# WDUExtensionBoard_v2.net
KiCad netlist of a schematic drawn in Altium Designer
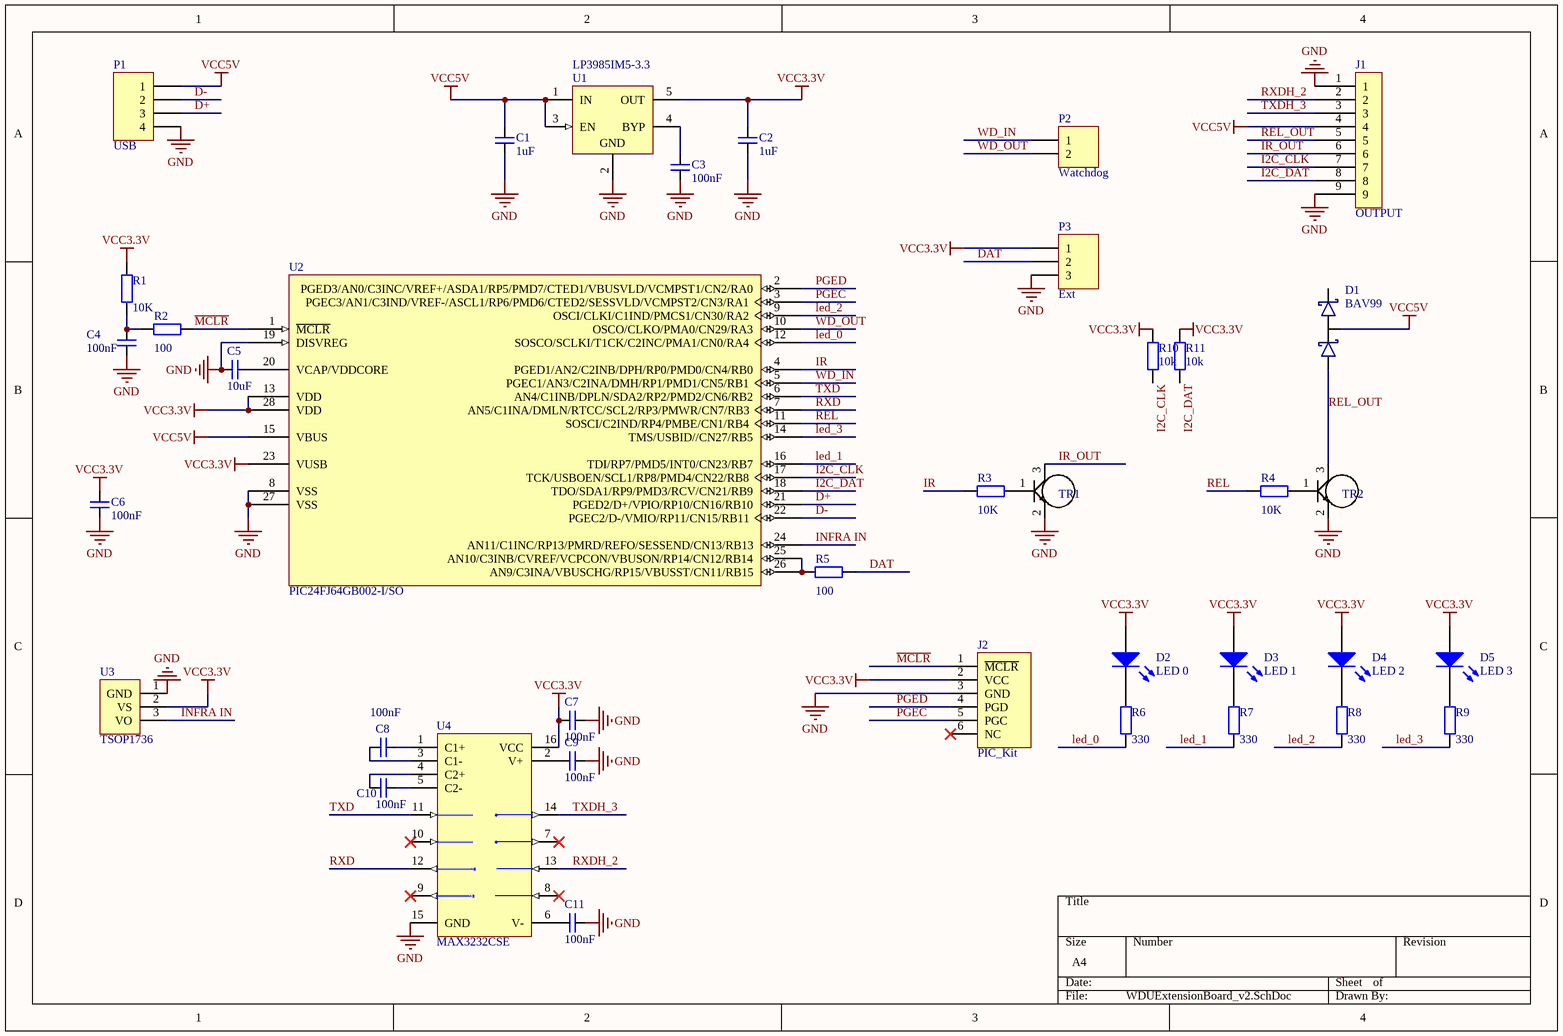
[diagram p0: WDUExtensionBoard_v2.SchDoc]

(export (version "E")
  (design (tool "Eeschema 10.0.6"))
  (components
    (comp (ref "C1")
      (value "1uF")
      (footprint "0805 CAP")
      (description "Capacitor")
      (libsource (lib "EtherIOv2") (part "CAP"))
    )
    (comp (ref "C2")
      (value "1uF")
      (footprint "0805 CAP")
      (description "Capacitor")
      (libsource (lib "EtherIOv2") (part "CAP"))
    )
    (comp (ref "C3")
      (value "100nF")
      (footprint "0805 CAP")
      (description "Capacitor")
      (libsource (lib "EtherIOv2") (part "CAP"))
    )
    (comp (ref "C4")
      (value "100nF")
      (footprint "0805 CAP")
      (description "Capacitor")
      (libsource (lib "EtherIOv2") (part "CAP"))
    )
    (comp (ref "C5")
      (value "10uF")
      (footprint "0805 CAP")
      (description "Capacitor")
      (libsource (lib "EtherIOv2") (part "CAP"))
    )
    (comp (ref "C6")
      (value "100nF")
      (footprint "0805 CAP")
      (description "Capacitor")
      (libsource (lib "EtherIOv2") (part "CAP"))
    )
    (comp (ref "C7")
      (value "100nF")
      (footprint "0805 CAP")
      (description "Capacitor")
      (libsource (lib "EtherIOv2") (part "CAP"))
    )
    (comp (ref "C8")
      (value "100nF")
      (footprint "0805 CAP")
      (description "Capacitor")
      (libsource (lib "EtherIOv2") (part "CAP"))
    )
    (comp (ref "C9")
      (value "100nF")
      (footprint "0805 CAP")
      (description "Capacitor")
      (libsource (lib "EtherIOv2") (part "CAP"))
    )
    (comp (ref "C10")
      (value "100nF")
      (footprint "0805 CAP")
      (description "Capacitor")
      (libsource (lib "EtherIOv2") (part "CAP"))
    )
    (comp (ref "C11")
      (value "100nF")
      (footprint "0805 CAP")
      (description "Capacitor")
      (libsource (lib "EtherIOv2") (part "CAP"))
    )
    (comp (ref "D1")
      (value "BAV99")
      (footprint "SOT23")
      (description "Dual Schottky series - 0.2A, 75V")
      (libsource (lib "EtherIOv2") (part "BAV99"))
    )
    (comp (ref "D2")
      (value "LED 0")
      (footprint "1206 LED Reversed")
      (description "Typical RED, GREEN, YELLOW, AMBER GaAs LED")
      (fields (field (name "PUBLISHER") "Altium Limited"))
      (libsource (lib "Miscellaneous Devices") (part "LED2"))
    )
    (comp (ref "D3")
      (value "LED 1")
      (footprint "1206 LED Reversed")
      (description "Typical RED, GREEN, YELLOW, AMBER GaAs LED")
      (fields (field (name "PUBLISHER") "Altium Limited"))
      (libsource (lib "Miscellaneous Devices") (part "LED2"))
    )
    (comp (ref "D4")
      (value "LED 2")
      (footprint "1206 LED Reversed")
      (description "Typical RED, GREEN, YELLOW, AMBER GaAs LED")
      (fields (field (name "PUBLISHER") "Altium Limited"))
      (libsource (lib "Miscellaneous Devices") (part "LED2"))
    )
    (comp (ref "D5")
      (value "LED 3")
      (footprint "1206 LED Reversed")
      (description "Typical RED, GREEN, YELLOW, AMBER GaAs LED")
      (fields (field (name "PUBLISHER") "Altium Limited"))
      (libsource (lib "Miscellaneous Devices") (part "LED2"))
    )
    (comp (ref "J1")
      (value "OUTPUT")
      (footprint "Euroblock 3.5pitch 9P")
      (libsource (lib "EtherIOv2") (part "Euroblock 9P connector"))
    )
    (comp (ref "J2")
      (value "PIC_Kit")
      (footprint "HDR1X6")
      (description "PIC Kit connector")
      (libsource (lib "EtherIOv2") (part "PIC_Kit"))
    )
    (comp (ref "P1")
      (value "USB")
      (footprint "HDR1X4")
      (description "Header, 4-Pin")
      (fields (field (name "PUBLISHER") "Altium Limited"))
      (libsource (lib "Miscellaneous Connectors") (part "Header 4"))
    )
    (comp (ref "P2")
      (value "Watchdog")
      (footprint "HDR1X2")
      (description "Header, 2-Pin")
      (fields (field (name "PUBLISHER") "Altium Limited"))
      (libsource (lib "Miscellaneous Connectors") (part "Header 2"))
    )
    (comp (ref "P3")
      (value "Ext")
      (footprint "HDR1X3")
      (description "Header, 3-Pin")
      (fields (field (name "PUBLISHER") "Altium Limited"))
      (libsource (lib "Miscellaneous Connectors") (part "Header 3"))
    )
    (comp (ref "R1")
      (value "10K")
      (footprint "0805 RES")
      (description "Resistor")
      (fields (field (name "PUBLISHER") "Altium Limited"))
      (libsource (lib "") (part "RES_1"))
    )
    (comp (ref "R2")
      (value "100")
      (footprint "0805 RES")
      (description "Resistor")
      (fields (field (name "PUBLISHER") "Altium Limited"))
      (libsource (lib "") (part "RES_2"))
    )
    (comp (ref "R3")
      (value "10K")
      (footprint "0805 RES")
      (description "Resistor")
      (fields (field (name "PUBLISHER") "Altium Limited"))
      (libsource (lib "") (part "RES_2"))
    )
    (comp (ref "R4")
      (value "10K")
      (footprint "0805 RES")
      (description "Resistor")
      (fields (field (name "PUBLISHER") "Altium Limited"))
      (libsource (lib "") (part "RES_2"))
    )
    (comp (ref "R5")
      (value "100")
      (footprint "0805 RES")
      (description "Resistor")
      (fields (field (name "PUBLISHER") "Altium Limited"))
      (libsource (lib "") (part "RES_2"))
    )
    (comp (ref "R6")
      (value "330")
      (footprint "0805 RES")
      (description "Resistor")
      (fields (field (name "PUBLISHER") "Altium Limited"))
      (libsource (lib "EtherIOv2") (part "RES"))
    )
    (comp (ref "R7")
      (value "330")
      (footprint "0805 RES")
      (description "Resistor")
      (fields (field (name "PUBLISHER") "Altium Limited"))
      (libsource (lib "EtherIOv2") (part "RES"))
    )
    (comp (ref "R8")
      (value "330")
      (footprint "0805 RES")
      (description "Resistor")
      (fields (field (name "PUBLISHER") "Altium Limited"))
      (libsource (lib "EtherIOv2") (part "RES"))
    )
    (comp (ref "R9")
      (value "330")
      (footprint "0805 RES")
      (description "Resistor")
      (fields (field (name "PUBLISHER") "Altium Limited"))
      (libsource (lib "EtherIOv2") (part "RES"))
    )
    (comp (ref "R10")
      (value "10k")
      (footprint "FP_0603_RES")
      (description "Resistor")
      (libsource (lib "Miscellaneous Devices") (part "Res3"))
    )
    (comp (ref "R11")
      (value "10k")
      (footprint "FP_0603_RES")
      (description "Resistor")
      (libsource (lib "Miscellaneous Devices") (part "Res3"))
    )
    (comp (ref "TR1")
      (value "BC846")
      (footprint "SOT23")
      (description "NPN Transistor, 80 V, SOT23")
      (libsource (lib "Waterstars") (part "BC846"))
    )
    (comp (ref "TR2")
      (value "BC846")
      (footprint "SOT23")
      (description "NPN Transistor, 80 V, SOT23")
      (libsource (lib "Waterstars") (part "BC846"))
    )
    (comp (ref "U1")
      (value "LP3985IM5-3.3")
      (footprint "MF05A_N")
      (description "Micropower, 150mA Low-Noise Ultra Low-Dropout CMOS Voltage Regulator")
      (fields
        (field (name "MANUFACTURER") "National Semiconductor")
        (field (name "DIGIKEYPARTNUMBER") "LP3985IM5-3.3CT-ND")
        (field (name "PUBLISHER") "Altium Limited")
      )
      (libsource (lib "NSC LDO") (part "LP3985IM5-3.3"))
    )
    (comp (ref "U2")
      (value "PIC24FJ64GB002-I/SO")
      (footprint "SSOP-28")
      (fields (field (name "PUBLISHER") "Altium Limited"))
      (libsource (lib "Waterstars") (part "PIC24FJ64GB002-I/SO"))
    )
    (comp (ref "U3")
      (value "TSOP1736")
      (footprint "TSOP17xx")
      (description "IR Receiver, 3-Pin")
      (fields (field (name "PUBLISHER") "Altium Limited"))
      (libsource (lib "EtherIOv2") (part "TSOP17xx"))
    )
    (comp (ref "U4")
      (value "MAX3232CSE")
      (footprint "NSO16_M")
      (description "3.0V TO 5.5V, Low-Power, up to 1Mbps, True RS-232 Transceiver Using Four 0.1µF External Capacitor")
      (fields (field (name "PUBLISHER") "Altium Limited"))
      (libsource (lib "Maxim Communication Transceiver") (part "MAX3232CSE"))
    )
  )
  (nets
    (net (code "1") (name "/D+") (class "Default")
      (node (ref "P1") (pin "3") (pinfunction "3_3") (pintype "passive"))
      (node (ref "U2") (pin "21") (pinfunction "PGED2/D+/VPIO/RP10/CN16/RB10_21") (pintype "bidirectional"))
    )
    (net (code "2") (name "/D-") (class "Default")
      (node (ref "P1") (pin "2") (pinfunction "2_2") (pintype "passive"))
      (node (ref "U2") (pin "22") (pinfunction "PGEC2/D-/VMIO/RP11/CN15/RB11_22") (pintype "bidirectional"))
    )
    (net (code "3") (name "/DAT") (class "Default")
      (node (ref "P3") (pin "2") (pinfunction "2_2") (pintype "passive"))
      (node (ref "R5") (pin "1") (pinfunction "1_1") (pintype "passive"))
    )
    (net (code "4") (name "/I2C_CLK") (class "Default")
      (node (ref "J1") (pin "7") (pinfunction "7_7") (pintype "passive"))
      (node (ref "R10") (pin "2") (pinfunction "2_2") (pintype "passive"))
      (node (ref "U2") (pin "17") (pinfunction "TCK/USBOEN/SCL1/RP8/PMD4/CN22/RB8_17") (pintype "bidirectional"))
    )
    (net (code "5") (name "/I2C_DAT") (class "Default")
      (node (ref "J1") (pin "8") (pinfunction "8_8") (pintype "passive"))
      (node (ref "R11") (pin "2") (pinfunction "2_2") (pintype "passive"))
      (node (ref "U2") (pin "18") (pinfunction "TDO/SDA1/RP9/PMD3/RCV/CN21/RB9_18") (pintype "bidirectional"))
    )
    (net (code "6") (name "/INFRA IN") (class "Default")
      (node (ref "U2") (pin "24") (pinfunction "AN11/C1INC/RP13/PMRD/REFO/SESSEND/CN13/RB13_24") (pintype "bidirectional"))
      (node (ref "U3") (pin "3") (pinfunction "VO_3") (pintype "passive"))
    )
    (net (code "7") (name "/IR") (class "Default")
      (node (ref "R3") (pin "2") (pinfunction "2_2") (pintype "passive"))
      (node (ref "U2") (pin "4") (pinfunction "PGED1/AN2/C2INB/DPH/RP0/PMD0/CN4/RB0_4") (pintype "bidirectional"))
    )
    (net (code "8") (name "/IR_OUT") (class "Default")
      (node (ref "J1") (pin "6") (pinfunction "6_6") (pintype "passive"))
      (node (ref "TR1") (pin "3") (pinfunction "2_3") (pintype "passive"))
    )
    (net (code "9") (name "/PGEC") (class "Default")
      (node (ref "J2") (pin "5") (pinfunction "PGC_5") (pintype "passive"))
      (node (ref "U2") (pin "3") (pinfunction "PGEC3/AN1/C3IND/VREF-/ASCL1/RP6/PMD6/CTED2/SESSVLD/VCMPST2/CN3/RA1_3") (pintype "bidirectional"))
    )
    (net (code "10") (name "/PGED") (class "Default")
      (node (ref "J2") (pin "4") (pinfunction "PGD_4") (pintype "passive"))
      (node (ref "U2") (pin "2") (pinfunction "PGED3/AN0/C3INC/VREF+/ASDA1/RP5/PMD7/CTED1/VBUSVLD/VCMPST1/CN2/RA0_2") (pintype "bidirectional"))
    )
    (net (code "11") (name "/REL") (class "Default")
      (node (ref "R4") (pin "2") (pinfunction "2_2") (pintype "passive"))
      (node (ref "U2") (pin "11") (pinfunction "SOSCI/C2IND/RP4/PMBE/CN1/RB4_11") (pintype "bidirectional"))
    )
    (net (code "12") (name "/REL_OUT") (class "Default")
      (node (ref "D1") (pin "1") (pintype "passive"))
      (node (ref "J1") (pin "5") (pinfunction "5_5") (pintype "passive"))
      (node (ref "TR2") (pin "3") (pinfunction "2_3") (pintype "passive"))
    )
    (net (code "13") (name "/RXD") (class "Default")
      (node (ref "U2") (pin "7") (pinfunction "AN5/C1INA/DMLN/RTCC/SCL2/RP3/PMWR/CN7/RB3_7") (pintype "bidirectional"))
      (node (ref "U4") (pin "12") (pinfunction "R1OUT_12") (pintype "output"))
    )
    (net (code "14") (name "/RXDH_2") (class "Default")
      (node (ref "J1") (pin "2") (pinfunction "2_2") (pintype "passive"))
      (node (ref "U4") (pin "13") (pinfunction "R1IN_13") (pintype "input"))
    )
    (net (code "15") (name "/TXD") (class "Default")
      (node (ref "U2") (pin "6") (pinfunction "AN4/C1INB/DPLN/SDA2/RP2/PMD2/CN6/RB2_6") (pintype "bidirectional"))
      (node (ref "U4") (pin "11") (pinfunction "T1IN_11") (pintype "input"))
    )
    (net (code "16") (name "/TXDH_3") (class "Default")
      (node (ref "J1") (pin "3") (pinfunction "3_3") (pintype "passive"))
      (node (ref "U4") (pin "14") (pinfunction "T1OUT_14") (pintype "output"))
    )
    (net (code "17") (name "/WD_IN") (class "Default")
      (node (ref "P2") (pin "1") (pinfunction "1_1") (pintype "passive"))
      (node (ref "U2") (pin "5") (pinfunction "PGEC1/AN3/C2INA/DMH/RP1/PMD1/CN5/RB1_5") (pintype "bidirectional"))
    )
    (net (code "18") (name "/WD_OUT") (class "Default")
      (node (ref "P2") (pin "2") (pinfunction "2_2") (pintype "passive"))
      (node (ref "U2") (pin "10") (pinfunction "OSCO/CLKO/PMA0/CN29/RA3_10") (pintype "bidirectional"))
    )
    (net (code "19") (name "/led_0") (class "Default")
      (node (ref "R6") (pin "2") (pinfunction "2_2") (pintype "passive"))
      (node (ref "U2") (pin "12") (pinfunction "SOSCO/SCLKI/T1CK/C2INC/PMA1/CN0/RA4_12") (pintype "bidirectional"))
    )
    (net (code "20") (name "/led_1") (class "Default")
      (node (ref "R7") (pin "2") (pinfunction "2_2") (pintype "passive"))
      (node (ref "U2") (pin "16") (pinfunction "TDI/RP7/PMD5/INT0/CN23/RB7_16") (pintype "bidirectional"))
    )
    (net (code "21") (name "/led_2") (class "Default")
      (node (ref "R8") (pin "2") (pinfunction "2_2") (pintype "passive"))
      (node (ref "U2") (pin "9") (pinfunction "OSCI/CLKI/C1IND/PMCS1/CN30/RA2_9") (pintype "bidirectional"))
    )
    (net (code "22") (name "/led_3") (class "Default")
      (node (ref "R9") (pin "2") (pinfunction "2_2") (pintype "passive"))
      (node (ref "U2") (pin "14") (pinfunction "TMS/USBID//CN27/RB5_14") (pintype "bidirectional"))
    )
    (net (code "23") (name "/~{MCLR}") (class "Default")
      (node (ref "J2") (pin "1") (pinfunction "~{MCLR}_1") (pintype "passive"))
      (node (ref "R2") (pin "1") (pinfunction "1_1") (pintype "passive"))
      (node (ref "U2") (pin "1") (pinfunction "~{MCLR}_1") (pintype "input"))
    )
    (net (code "24") (name "GND") (class "Default")
      (node (ref "C1") (pin "1") (pinfunction "A_1") (pintype "passive"))
      (node (ref "C11") (pin "2") (pinfunction "B_2") (pintype "passive"))
      (node (ref "C2") (pin "1") (pinfunction "A_1") (pintype "passive"))
      (node (ref "C3") (pin "1") (pinfunction "A_1") (pintype "passive"))
      (node (ref "C4") (pin "1") (pinfunction "A_1") (pintype "passive"))
      (node (ref "C5") (pin "2") (pinfunction "B_2") (pintype "passive"))
      (node (ref "C6") (pin "1") (pinfunction "A_1") (pintype "passive"))
      (node (ref "C7") (pin "2") (pinfunction "B_2") (pintype "passive"))
      (node (ref "C9") (pin "2") (pinfunction "B_2") (pintype "passive"))
      (node (ref "J1") (pin "1") (pinfunction "1_1") (pintype "passive"))
      (node (ref "J1") (pin "9") (pinfunction "9_9") (pintype "passive"))
      (node (ref "J2") (pin "3") (pinfunction "GND_3") (pintype "passive"))
      (node (ref "P1") (pin "4") (pinfunction "4_4") (pintype "passive"))
      (node (ref "P3") (pin "3") (pinfunction "3_3") (pintype "passive"))
      (node (ref "TR1") (pin "2") (pinfunction "1_2") (pintype "passive"))
      (node (ref "TR2") (pin "2") (pinfunction "1_2") (pintype "passive"))
      (node (ref "U1") (pin "2") (pinfunction "GND_2") (pintype "power_in"))
      (node (ref "U2") (pin "19") (pinfunction "DISVREG_19") (pintype "input"))
      (node (ref "U2") (pin "27") (pinfunction "VSS_27") (pintype "power_in"))
      (node (ref "U2") (pin "8") (pinfunction "VSS_8") (pintype "power_in"))
      (node (ref "U3") (pin "1") (pinfunction "GND_1") (pintype "passive"))
      (node (ref "U4") (pin "15") (pinfunction "GND_15") (pintype "power_in"))
    )
    (net (code "25") (name "Net-(C3-B)") (class "Default")
      (node (ref "C3") (pin "2") (pinfunction "B_2") (pintype "passive"))
      (node (ref "U1") (pin "4") (pinfunction "BYP_4") (pintype "passive"))
    )
    (net (code "26") (name "Net-(C4-B)") (class "Default")
      (node (ref "C4") (pin "2") (pinfunction "B_2") (pintype "passive"))
      (node (ref "R1") (pin "1") (pinfunction "1_1") (pintype "passive"))
      (node (ref "R2") (pin "2") (pinfunction "2_2") (pintype "passive"))
    )
    (net (code "27") (name "Net-(C5-A)") (class "Default")
      (node (ref "C5") (pin "1") (pinfunction "A_1") (pintype "passive"))
      (node (ref "U2") (pin "20") (pinfunction "VCAP/VDDCORE_20") (pintype "power_in"))
    )
    (net (code "28") (name "Net-(C8-A)") (class "Default")
      (node (ref "C8") (pin "1") (pinfunction "A_1") (pintype "passive"))
      (node (ref "U4") (pin "3") (pinfunction "C1-_3") (pintype "passive"))
    )
    (net (code "29") (name "Net-(C8-B)") (class "Default")
      (node (ref "C8") (pin "2") (pinfunction "B_2") (pintype "passive"))
      (node (ref "U4") (pin "1") (pinfunction "C1+_1") (pintype "passive"))
    )
    (net (code "30") (name "Net-(C9-A)") (class "Default")
      (node (ref "C9") (pin "1") (pinfunction "A_1") (pintype "passive"))
      (node (ref "U4") (pin "2") (pinfunction "V+_2") (pintype "power_in"))
    )
    (net (code "31") (name "Net-(C10-A)") (class "Default")
      (node (ref "C10") (pin "1") (pinfunction "A_1") (pintype "passive"))
      (node (ref "U4") (pin "4") (pinfunction "C2+_4") (pintype "passive"))
    )
    (net (code "32") (name "Net-(C10-B)") (class "Default")
      (node (ref "C10") (pin "2") (pinfunction "B_2") (pintype "passive"))
      (node (ref "U4") (pin "5") (pinfunction "C2-_5") (pintype "passive"))
    )
    (net (code "33") (name "Net-(C11-A)") (class "Default")
      (node (ref "C11") (pin "1") (pinfunction "A_1") (pintype "passive"))
      (node (ref "U4") (pin "6") (pinfunction "V-_6") (pintype "power_in"))
    )
    (net (code "34") (name "Net-(D2-K)") (class "Default")
      (node (ref "D2") (pin "2") (pinfunction "K_2") (pintype "passive"))
      (node (ref "R6") (pin "1") (pinfunction "1_1") (pintype "passive"))
    )
    (net (code "35") (name "Net-(D3-K)") (class "Default")
      (node (ref "D3") (pin "2") (pinfunction "K_2") (pintype "passive"))
      (node (ref "R7") (pin "1") (pinfunction "1_1") (pintype "passive"))
    )
    (net (code "36") (name "Net-(D4-K)") (class "Default")
      (node (ref "D4") (pin "2") (pinfunction "K_2") (pintype "passive"))
      (node (ref "R8") (pin "1") (pinfunction "1_1") (pintype "passive"))
    )
    (net (code "37") (name "Net-(D5-K)") (class "Default")
      (node (ref "D5") (pin "2") (pinfunction "K_2") (pintype "passive"))
      (node (ref "R9") (pin "1") (pinfunction "1_1") (pintype "passive"))
    )
    (net (code "38") (name "Net-(TR1-B)") (class "Default")
      (node (ref "R3") (pin "1") (pinfunction "1_1") (pintype "passive"))
      (node (ref "TR1") (pin "1") (pinfunction "B_1") (pintype "passive"))
    )
    (net (code "39") (name "Net-(TR2-B)") (class "Default")
      (node (ref "R4") (pin "1") (pinfunction "1_1") (pintype "passive"))
      (node (ref "TR2") (pin "1") (pinfunction "B_1") (pintype "passive"))
    )
    (net (code "40") (name "Net-(U2-AN10{slash}C3INB{slash}CVREF{slash}VCPCON{slash}VBUSON{slash}RP14{slash}CN12{slash}RB14)") (class "Default")
      (node (ref "R5") (pin "2") (pinfunction "2_2") (pintype "passive"))
      (node (ref "U2") (pin "25") (pinfunction "AN10/C3INB/CVREF/VCPCON/VBUSON/RP14/CN12/RB14_25") (pintype "bidirectional"))
      (node (ref "U2") (pin "26") (pinfunction "AN9/C3INA/VBUSCHG/RP15/VBUSST/CN11/RB15_26") (pintype "bidirectional"))
    )
    (net (code "41") (name "VCC3.3V") (class "Default")
      (node (ref "C2") (pin "2") (pinfunction "B_2") (pintype "passive"))
      (node (ref "C6") (pin "2") (pinfunction "B_2") (pintype "passive"))
      (node (ref "C7") (pin "1") (pinfunction "A_1") (pintype "passive"))
      (node (ref "D2") (pin "1") (pinfunction "A_1") (pintype "passive"))
      (node (ref "D3") (pin "1") (pinfunction "A_1") (pintype "passive"))
      (node (ref "D4") (pin "1") (pinfunction "A_1") (pintype "passive"))
      (node (ref "D5") (pin "1") (pinfunction "A_1") (pintype "passive"))
      (node (ref "J2") (pin "2") (pinfunction "VCC_2") (pintype "passive"))
      (node (ref "P3") (pin "1") (pinfunction "1_1") (pintype "passive"))
      (node (ref "R1") (pin "2") (pinfunction "2_2") (pintype "passive"))
      (node (ref "R10") (pin "1") (pinfunction "1_1") (pintype "passive"))
      (node (ref "R11") (pin "1") (pinfunction "1_1") (pintype "passive"))
      (node (ref "U1") (pin "5") (pinfunction "OUT_5") (pintype "power_in"))
      (node (ref "U2") (pin "13") (pinfunction "VDD_13") (pintype "power_in"))
      (node (ref "U2") (pin "23") (pinfunction "VUSB_23") (pintype "power_in"))
      (node (ref "U2") (pin "28") (pinfunction "VDD_28") (pintype "power_in"))
      (node (ref "U3") (pin "2") (pinfunction "VS_2") (pintype "passive"))
      (node (ref "U4") (pin "16") (pinfunction "VCC_16") (pintype "power_in"))
    )
    (net (code "42") (name "VCC5V") (class "Default")
      (node (ref "C1") (pin "2") (pinfunction "B_2") (pintype "passive"))
      (node (ref "D1") (pin "3") (pintype "passive"))
      (node (ref "J1") (pin "4") (pinfunction "4_4") (pintype "passive"))
      (node (ref "P1") (pin "1") (pinfunction "1_1") (pintype "passive"))
      (node (ref "U1") (pin "1") (pinfunction "IN_1") (pintype "power_in"))
      (node (ref "U1") (pin "3") (pinfunction "EN_3") (pintype "input"))
      (node (ref "U2") (pin "15") (pinfunction "VBUS_15") (pintype "power_in"))
    )
    (net (code "43") (name "unconnected-(D1-Pad2)") (class "Default")
      (node (ref "D1") (pin "2") (pintype "passive"))
    )
    (net (code "44") (name "unconnected-(J2-NC-Pad6)") (class "Default")
      (node (ref "J2") (pin "6") (pinfunction "NC_6") (pintype "passive+no_connect"))
    )
    (net (code "45") (name "unconnected-(U4-R2IN-Pad8)") (class "Default")
      (node (ref "U4") (pin "8") (pinfunction "R2IN_8") (pintype "input+no_connect"))
    )
    (net (code "46") (name "unconnected-(U4-R2OUT-Pad9)") (class "Default")
      (node (ref "U4") (pin "9") (pinfunction "R2OUT_9") (pintype "output+no_connect"))
    )
    (net (code "47") (name "unconnected-(U4-T2IN-Pad10)") (class "Default")
      (node (ref "U4") (pin "10") (pinfunction "T2IN_10") (pintype "input+no_connect"))
    )
    (net (code "48") (name "unconnected-(U4-T2OUT-Pad7)") (class "Default")
      (node (ref "U4") (pin "7") (pinfunction "T2OUT_7") (pintype "output+no_connect"))
    )
  )
)
